# detectino.net
KiCad netlist of a schematic drawn in EAGLE
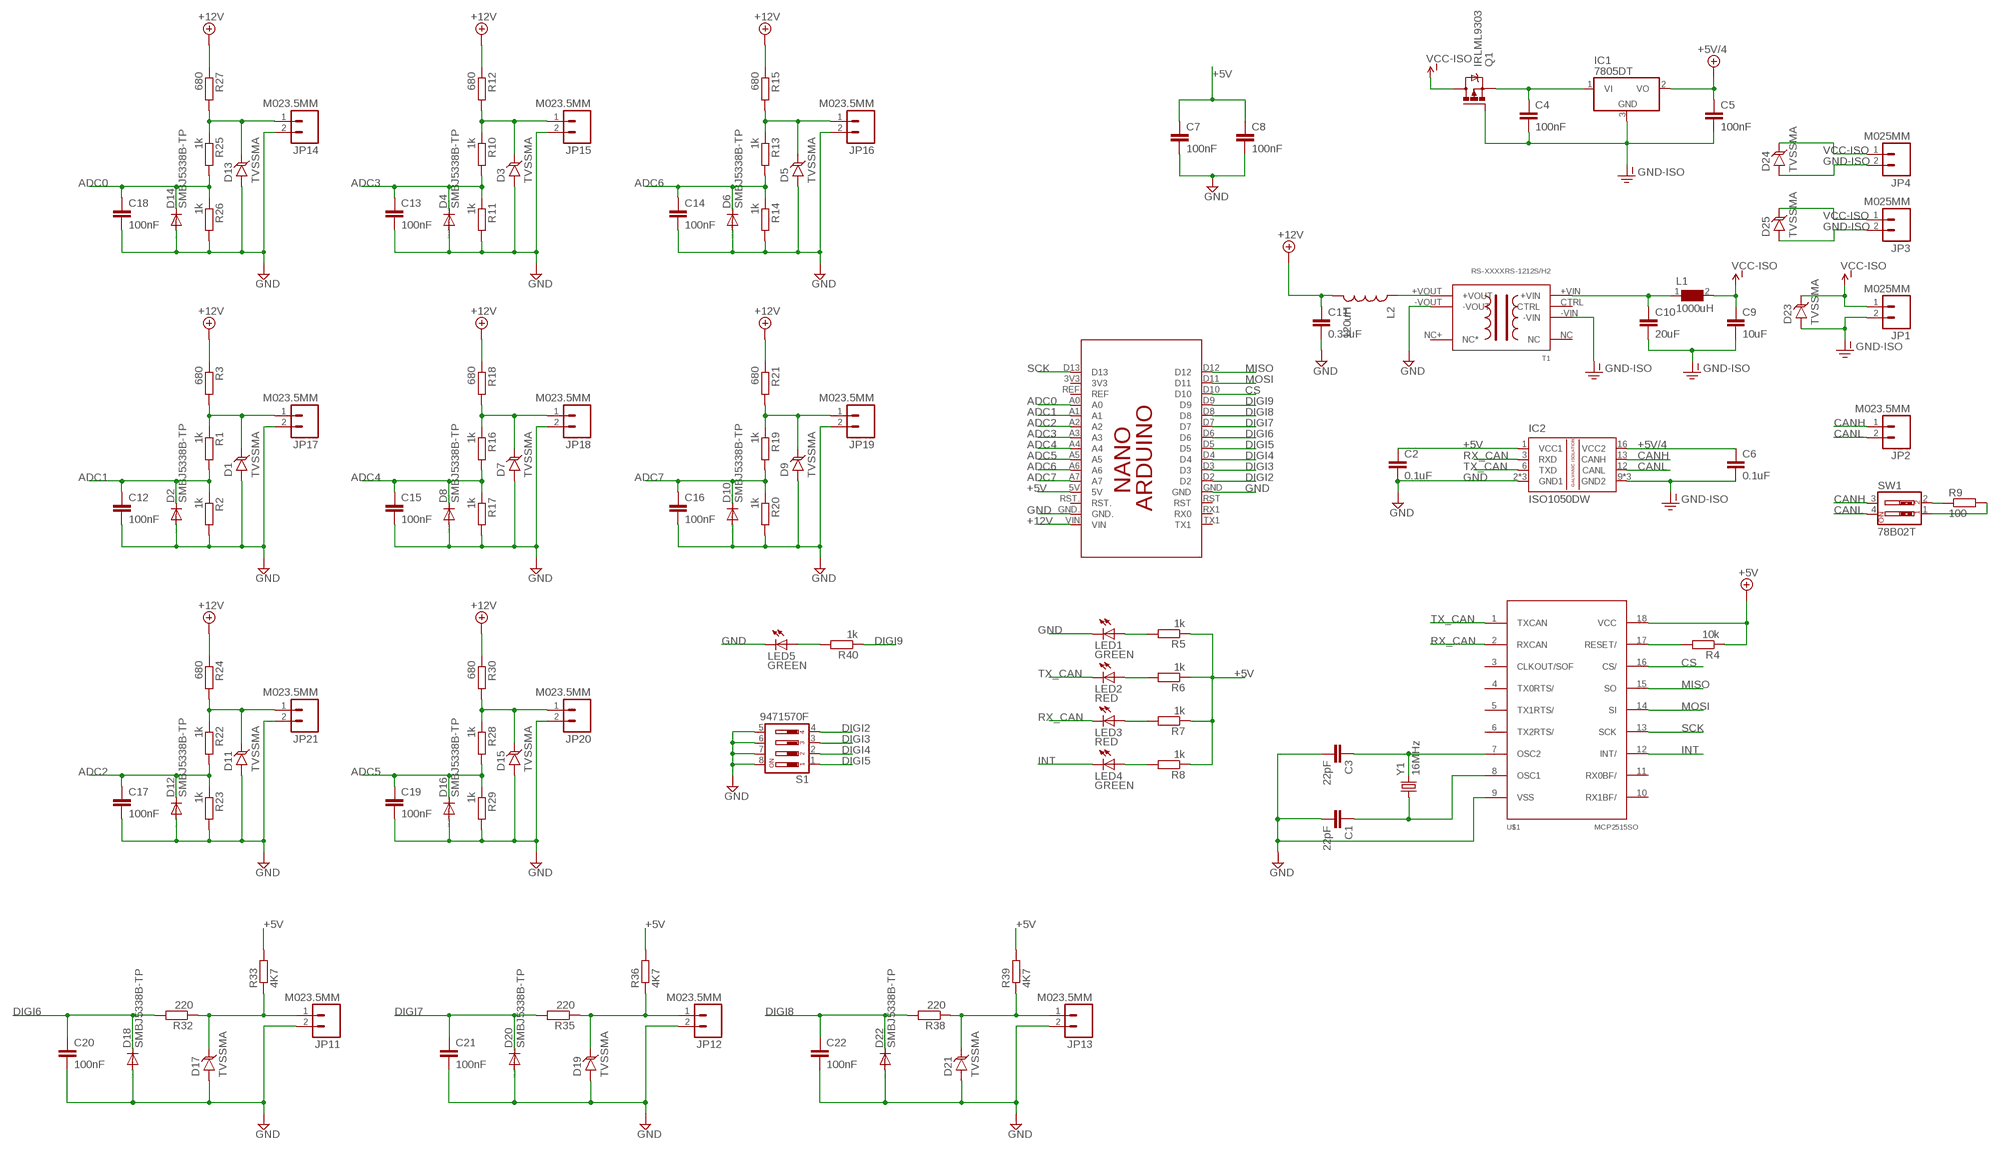
[diagram p0: schematic, sheet 1]

(export (version "E")
  (design (tool "Eeschema 10.0.6"))
  (components
    (comp (ref "C1")
      (value "22pF")
      (footprint "eagle-import:C0805K")
      (libsource (lib "eagle-import") (part "C-EUC0805K"))
    )
    (comp (ref "C2")
      (value "0.1uF")
      (footprint "eagle-import:C0805K")
      (libsource (lib "eagle-import") (part "C-EUC0805K"))
    )
    (comp (ref "C3")
      (value "22pF")
      (footprint "eagle-import:C0805K")
      (libsource (lib "eagle-import") (part "C-EUC0805K"))
    )
    (comp (ref "C4")
      (value "100nF")
      (footprint "eagle-import:C0805K")
      (libsource (lib "eagle-import") (part "C-EUC0805K"))
    )
    (comp (ref "C5")
      (value "100nF")
      (footprint "eagle-import:C0805K")
      (libsource (lib "eagle-import") (part "C-EUC0805K"))
    )
    (comp (ref "C6")
      (value "0.1uF")
      (footprint "eagle-import:C0805K")
      (libsource (lib "eagle-import") (part "C-EUC0805K"))
    )
    (comp (ref "C7")
      (value "100nF")
      (footprint "eagle-import:C0805K")
      (libsource (lib "eagle-import") (part "C-EUC0805K"))
    )
    (comp (ref "C8")
      (value "100nF")
      (footprint "eagle-import:C0805K")
      (libsource (lib "eagle-import") (part "C-EUC0805K"))
    )
    (comp (ref "C9")
      (value "10uF")
      (footprint "eagle-import:C0805K")
      (libsource (lib "eagle-import") (part "C-EUC0805K"))
    )
    (comp (ref "C10")
      (value "20uF")
      (footprint "eagle-import:C0805K")
      (libsource (lib "eagle-import") (part "C-EUC0805K"))
    )
    (comp (ref "C11")
      (value "0.33uF")
      (footprint "eagle-import:C0805K")
      (libsource (lib "eagle-import") (part "C-EUC0805K"))
    )
    (comp (ref "C12")
      (value "100nF")
      (footprint "eagle-import:C0805K")
      (libsource (lib "eagle-import") (part "C-EUC0805K"))
    )
    (comp (ref "C13")
      (value "100nF")
      (footprint "eagle-import:C0805K")
      (libsource (lib "eagle-import") (part "C-EUC0805K"))
    )
    (comp (ref "C14")
      (value "100nF")
      (footprint "eagle-import:C0805K")
      (libsource (lib "eagle-import") (part "C-EUC0805K"))
    )
    (comp (ref "C15")
      (value "100nF")
      (footprint "eagle-import:C0805K")
      (libsource (lib "eagle-import") (part "C-EUC0805K"))
    )
    (comp (ref "C16")
      (value "100nF")
      (footprint "eagle-import:C0805K")
      (libsource (lib "eagle-import") (part "C-EUC0805K"))
    )
    (comp (ref "C17")
      (value "100nF")
      (footprint "eagle-import:C0805K")
      (libsource (lib "eagle-import") (part "C-EUC0805K"))
    )
    (comp (ref "C18")
      (value "100nF")
      (footprint "eagle-import:C0805K")
      (libsource (lib "eagle-import") (part "C-EUC0805K"))
    )
    (comp (ref "C19")
      (value "100nF")
      (footprint "eagle-import:C0805K")
      (libsource (lib "eagle-import") (part "C-EUC0805K"))
    )
    (comp (ref "C20")
      (value "100nF")
      (footprint "eagle-import:C0805K")
      (libsource (lib "eagle-import") (part "C-EUC0805K"))
    )
    (comp (ref "C21")
      (value "100nF")
      (footprint "eagle-import:C0805K")
      (libsource (lib "eagle-import") (part "C-EUC0805K"))
    )
    (comp (ref "C22")
      (value "100nF")
      (footprint "eagle-import:C0805K")
      (libsource (lib "eagle-import") (part "C-EUC0805K"))
    )
    (comp (ref "D1")
      (value "TVSSMA")
      (footprint "eagle-import:SMA-DIODE")
      (libsource (lib "eagle-import") (part "TVSSMA"))
    )
    (comp (ref "D2")
      (value "SMBJ5338B-TP")
      (footprint "eagle-import:DO214AA")
      (libsource (lib "eagle-import") (part "DIODE-DO214AA"))
    )
    (comp (ref "D3")
      (value "TVSSMA")
      (footprint "eagle-import:SMA-DIODE")
      (libsource (lib "eagle-import") (part "TVSSMA"))
    )
    (comp (ref "D4")
      (value "SMBJ5338B-TP")
      (footprint "eagle-import:DO214AA")
      (libsource (lib "eagle-import") (part "DIODE-DO214AA"))
    )
    (comp (ref "D5")
      (value "TVSSMA")
      (footprint "eagle-import:SMA-DIODE")
      (libsource (lib "eagle-import") (part "TVSSMA"))
    )
    (comp (ref "D6")
      (value "SMBJ5338B-TP")
      (footprint "eagle-import:DO214AA")
      (libsource (lib "eagle-import") (part "DIODE-DO214AA"))
    )
    (comp (ref "D7")
      (value "TVSSMA")
      (footprint "eagle-import:SMA-DIODE")
      (libsource (lib "eagle-import") (part "TVSSMA"))
    )
    (comp (ref "D8")
      (value "SMBJ5338B-TP")
      (footprint "eagle-import:DO214AA")
      (libsource (lib "eagle-import") (part "DIODE-DO214AA"))
    )
    (comp (ref "D9")
      (value "TVSSMA")
      (footprint "eagle-import:SMA-DIODE")
      (libsource (lib "eagle-import") (part "TVSSMA"))
    )
    (comp (ref "D10")
      (value "SMBJ5338B-TP")
      (footprint "eagle-import:DO214AA")
      (libsource (lib "eagle-import") (part "DIODE-DO214AA"))
    )
    (comp (ref "D11")
      (value "TVSSMA")
      (footprint "eagle-import:SMA-DIODE")
      (libsource (lib "eagle-import") (part "TVSSMA"))
    )
    (comp (ref "D12")
      (value "SMBJ5338B-TP")
      (footprint "eagle-import:DO214AA")
      (libsource (lib "eagle-import") (part "DIODE-DO214AA"))
    )
    (comp (ref "D13")
      (value "TVSSMA")
      (footprint "eagle-import:SMA-DIODE")
      (libsource (lib "eagle-import") (part "TVSSMA"))
    )
    (comp (ref "D14")
      (value "SMBJ5338B-TP")
      (footprint "eagle-import:DO214AA")
      (libsource (lib "eagle-import") (part "DIODE-DO214AA"))
    )
    (comp (ref "D15")
      (value "TVSSMA")
      (footprint "eagle-import:SMA-DIODE")
      (libsource (lib "eagle-import") (part "TVSSMA"))
    )
    (comp (ref "D16")
      (value "SMBJ5338B-TP")
      (footprint "eagle-import:DO214AA")
      (libsource (lib "eagle-import") (part "DIODE-DO214AA"))
    )
    (comp (ref "D17")
      (value "TVSSMA")
      (footprint "eagle-import:SMA-DIODE")
      (libsource (lib "eagle-import") (part "TVSSMA"))
    )
    (comp (ref "D18")
      (value "SMBJ5338B-TP")
      (footprint "eagle-import:DO214AA")
      (libsource (lib "eagle-import") (part "DIODE-DO214AA"))
    )
    (comp (ref "D19")
      (value "TVSSMA")
      (footprint "eagle-import:SMA-DIODE")
      (libsource (lib "eagle-import") (part "TVSSMA"))
    )
    (comp (ref "D20")
      (value "SMBJ5338B-TP")
      (footprint "eagle-import:DO214AA")
      (libsource (lib "eagle-import") (part "DIODE-DO214AA"))
    )
    (comp (ref "D21")
      (value "TVSSMA")
      (footprint "eagle-import:SMA-DIODE")
      (libsource (lib "eagle-import") (part "TVSSMA"))
    )
    (comp (ref "D22")
      (value "SMBJ5338B-TP")
      (footprint "eagle-import:DO214AA")
      (libsource (lib "eagle-import") (part "DIODE-DO214AA"))
    )
    (comp (ref "D23")
      (value "TVSSMA")
      (footprint "eagle-import:SMA-DIODE")
      (libsource (lib "eagle-import") (part "TVSSMA"))
    )
    (comp (ref "D24")
      (value "TVSSMA")
      (footprint "eagle-import:SMA-DIODE")
      (libsource (lib "eagle-import") (part "TVSSMA"))
    )
    (comp (ref "D25")
      (value "TVSSMA")
      (footprint "eagle-import:SMA-DIODE")
      (libsource (lib "eagle-import") (part "TVSSMA"))
    )
    (comp (ref "IC1")
      (value "7805DT")
      (footprint "eagle-import:TO252")
      (libsource (lib "eagle-import") (part "78DT05"))
    )
    (comp (ref "IC2")
      (value "ISO1050DW")
      (footprint "eagle-import:SO-16DW")
      (libsource (lib "eagle-import") (part "ISO1050DW"))
    )
    (comp (ref "JP1")
      (value "M025MM")
      (footprint "eagle-import:SCREWTERMINAL-5MM-2")
      (libsource (lib "eagle-import") (part "M025MM"))
    )
    (comp (ref "JP2")
      (value "M023.5MM")
      (footprint "eagle-import:SCREWTERMINAL-3.5MM-2")
      (libsource (lib "eagle-import") (part "M023.5MM"))
    )
    (comp (ref "JP3")
      (value "M025MM")
      (footprint "eagle-import:SCREWTERMINAL-5MM-2")
      (libsource (lib "eagle-import") (part "M025MM"))
    )
    (comp (ref "JP4")
      (value "M025MM")
      (footprint "eagle-import:SCREWTERMINAL-5MM-2")
      (libsource (lib "eagle-import") (part "M025MM"))
    )
    (comp (ref "JP11")
      (value "M023.5MM")
      (footprint "eagle-import:SCREWTERMINAL-3.5MM-2")
      (libsource (lib "eagle-import") (part "M023.5MM"))
    )
    (comp (ref "JP12")
      (value "M023.5MM")
      (footprint "eagle-import:SCREWTERMINAL-3.5MM-2")
      (libsource (lib "eagle-import") (part "M023.5MM"))
    )
    (comp (ref "JP13")
      (value "M023.5MM")
      (footprint "eagle-import:SCREWTERMINAL-3.5MM-2")
      (libsource (lib "eagle-import") (part "M023.5MM"))
    )
    (comp (ref "JP14")
      (value "M023.5MM")
      (footprint "eagle-import:SCREWTERMINAL-3.5MM-2")
      (libsource (lib "eagle-import") (part "M023.5MM"))
    )
    (comp (ref "JP15")
      (value "M023.5MM")
      (footprint "eagle-import:SCREWTERMINAL-3.5MM-2")
      (libsource (lib "eagle-import") (part "M023.5MM"))
    )
    (comp (ref "JP16")
      (value "M023.5MM")
      (footprint "eagle-import:SCREWTERMINAL-3.5MM-2")
      (libsource (lib "eagle-import") (part "M023.5MM"))
    )
    (comp (ref "JP17")
      (value "M023.5MM")
      (footprint "eagle-import:SCREWTERMINAL-3.5MM-2")
      (libsource (lib "eagle-import") (part "M023.5MM"))
    )
    (comp (ref "JP18")
      (value "M023.5MM")
      (footprint "eagle-import:SCREWTERMINAL-3.5MM-2")
      (libsource (lib "eagle-import") (part "M023.5MM"))
    )
    (comp (ref "JP19")
      (value "M023.5MM")
      (footprint "eagle-import:SCREWTERMINAL-3.5MM-2")
      (libsource (lib "eagle-import") (part "M023.5MM"))
    )
    (comp (ref "JP20")
      (value "M023.5MM")
      (footprint "eagle-import:SCREWTERMINAL-3.5MM-2")
      (libsource (lib "eagle-import") (part "M023.5MM"))
    )
    (comp (ref "JP21")
      (value "M023.5MM")
      (footprint "eagle-import:SCREWTERMINAL-3.5MM-2")
      (libsource (lib "eagle-import") (part "M023.5MM"))
    )
    (comp (ref "L1")
      (value "1000uH")
      (footprint "eagle-import:WE-TIS_1111")
      (fields (field (name "MPN") "7447471102"))
      (libsource (lib "eagle-import") (part "WE-TIS_1111-7447471102"))
    )
    (comp (ref "L2")
      (value "120uH")
      (footprint "eagle-import:SDR0403")
      (libsource (lib "eagle-import") (part "INDUCTORSDR0403-560KL"))
    )
    (comp (ref "LED1")
      (value "GREEN")
      (footprint "eagle-import:SML0805")
      (libsource (lib "eagle-import") (part "LEDSML0805"))
    )
    (comp (ref "LED2")
      (value "RED")
      (footprint "eagle-import:SML0805")
      (libsource (lib "eagle-import") (part "LEDSML0805"))
    )
    (comp (ref "LED3")
      (value "RED")
      (footprint "eagle-import:SML0805")
      (libsource (lib "eagle-import") (part "LEDSML0805"))
    )
    (comp (ref "LED4")
      (value "GREEN")
      (footprint "eagle-import:SML0805")
      (libsource (lib "eagle-import") (part "LEDSML0805"))
    )
    (comp (ref "LED5")
      (value "GREEN")
      (footprint "eagle-import:SML0805")
      (libsource (lib "eagle-import") (part "LEDSML0805"))
    )
    (comp (ref "PCB2")
      (value "ARDUINO_NANO")
      (footprint "eagle-import:ARDUINO_NANO")
      (libsource (lib "eagle-import") (part "ARDUINO_NANO"))
    )
    (comp (ref "Q1")
      (value "IRLML9303")
      (footprint "eagle-import:MICRO3")
      (libsource (lib "eagle-import") (part "IRLML5203"))
    )
    (comp (ref "R1")
      (value "1k")
      (footprint "eagle-import:0204_5")
      (libsource (lib "eagle-import") (part "R-EU_0204/5"))
    )
    (comp (ref "R2")
      (value "1k")
      (footprint "eagle-import:0204_5")
      (libsource (lib "eagle-import") (part "R-EU_0204/5"))
    )
    (comp (ref "R3")
      (value "680")
      (footprint "eagle-import:0204_5")
      (libsource (lib "eagle-import") (part "R-EU_0204/5"))
    )
    (comp (ref "R4")
      (value "10k")
      (footprint "eagle-import:R0805W")
      (libsource (lib "eagle-import") (part "R-EU_R0805W"))
    )
    (comp (ref "R5")
      (value "1k")
      (footprint "eagle-import:0204_5")
      (libsource (lib "eagle-import") (part "R-EU_0204/5"))
    )
    (comp (ref "R6")
      (value "1k")
      (footprint "eagle-import:0204_5")
      (libsource (lib "eagle-import") (part "R-EU_0204/5"))
    )
    (comp (ref "R7")
      (value "1k")
      (footprint "eagle-import:0204_5")
      (libsource (lib "eagle-import") (part "R-EU_0204/5"))
    )
    (comp (ref "R8")
      (value "1k")
      (footprint "eagle-import:0204_5")
      (libsource (lib "eagle-import") (part "R-EU_0204/5"))
    )
    (comp (ref "R9")
      (value "100")
      (footprint "eagle-import:R0805W")
      (libsource (lib "eagle-import") (part "R-EU_R0805W"))
    )
    (comp (ref "R10")
      (value "1k")
      (footprint "eagle-import:0204_5")
      (libsource (lib "eagle-import") (part "R-EU_0204/5"))
    )
    (comp (ref "R11")
      (value "1k")
      (footprint "eagle-import:0204_5")
      (libsource (lib "eagle-import") (part "R-EU_0204/5"))
    )
    (comp (ref "R12")
      (value "680")
      (footprint "eagle-import:0204_5")
      (libsource (lib "eagle-import") (part "R-EU_0204/5"))
    )
    (comp (ref "R13")
      (value "1k")
      (footprint "eagle-import:0204_5")
      (libsource (lib "eagle-import") (part "R-EU_0204/5"))
    )
    (comp (ref "R14")
      (value "1k")
      (footprint "eagle-import:0204_5")
      (libsource (lib "eagle-import") (part "R-EU_0204/5"))
    )
    (comp (ref "R15")
      (value "680")
      (footprint "eagle-import:0204_5")
      (libsource (lib "eagle-import") (part "R-EU_0204/5"))
    )
    (comp (ref "R16")
      (value "1k")
      (footprint "eagle-import:0204_5")
      (libsource (lib "eagle-import") (part "R-EU_0204/5"))
    )
    (comp (ref "R17")
      (value "1k")
      (footprint "eagle-import:0204_5")
      (libsource (lib "eagle-import") (part "R-EU_0204/5"))
    )
    (comp (ref "R18")
      (value "680")
      (footprint "eagle-import:0204_5")
      (libsource (lib "eagle-import") (part "R-EU_0204/5"))
    )
    (comp (ref "R19")
      (value "1k")
      (footprint "eagle-import:0204_5")
      (libsource (lib "eagle-import") (part "R-EU_0204/5"))
    )
    (comp (ref "R20")
      (value "1k")
      (footprint "eagle-import:0204_5")
      (libsource (lib "eagle-import") (part "R-EU_0204/5"))
    )
    (comp (ref "R21")
      (value "680")
      (footprint "eagle-import:0204_5")
      (libsource (lib "eagle-import") (part "R-EU_0204/5"))
    )
    (comp (ref "R22")
      (value "1k")
      (footprint "eagle-import:0204_5")
      (libsource (lib "eagle-import") (part "R-EU_0204/5"))
    )
    (comp (ref "R23")
      (value "1k")
      (footprint "eagle-import:0204_5")
      (libsource (lib "eagle-import") (part "R-EU_0204/5"))
    )
    (comp (ref "R24")
      (value "680")
      (footprint "eagle-import:0204_5")
      (libsource (lib "eagle-import") (part "R-EU_0204/5"))
    )
    (comp (ref "R25")
      (value "1k")
      (footprint "eagle-import:0204_5")
      (libsource (lib "eagle-import") (part "R-EU_0204/5"))
    )
    (comp (ref "R26")
      (value "1k")
      (footprint "eagle-import:0204_5")
      (libsource (lib "eagle-import") (part "R-EU_0204/5"))
    )
    (comp (ref "R27")
      (value "680")
      (footprint "eagle-import:0204_5")
      (libsource (lib "eagle-import") (part "R-EU_0204/5"))
    )
    (comp (ref "R28")
      (value "1k")
      (footprint "eagle-import:0204_5")
      (libsource (lib "eagle-import") (part "R-EU_0204/5"))
    )
    (comp (ref "R29")
      (value "1k")
      (footprint "eagle-import:0204_5")
      (libsource (lib "eagle-import") (part "R-EU_0204/5"))
    )
    (comp (ref "R30")
      (value "680")
      (footprint "eagle-import:0204_5")
      (libsource (lib "eagle-import") (part "R-EU_0204/5"))
    )
    (comp (ref "R32")
      (value "220")
      (footprint "eagle-import:0204_5")
      (libsource (lib "eagle-import") (part "R-EU_0204/5"))
    )
    (comp (ref "R33")
      (value "4K7")
      (footprint "eagle-import:0204_5")
      (libsource (lib "eagle-import") (part "R-EU_0204/5"))
    )
    (comp (ref "R35")
      (value "220")
      (footprint "eagle-import:0204_5")
      (libsource (lib "eagle-import") (part "R-EU_0204/5"))
    )
    (comp (ref "R36")
      (value "4K7")
      (footprint "eagle-import:0204_5")
      (libsource (lib "eagle-import") (part "R-EU_0204/5"))
    )
    (comp (ref "R38")
      (value "220")
      (footprint "eagle-import:0204_5")
      (libsource (lib "eagle-import") (part "R-EU_0204/5"))
    )
    (comp (ref "R39")
      (value "4K7")
      (footprint "eagle-import:0204_5")
      (libsource (lib "eagle-import") (part "R-EU_0204/5"))
    )
    (comp (ref "R40")
      (value "1k")
      (footprint "eagle-import:0204_5")
      (libsource (lib "eagle-import") (part "R-EU_0204/5"))
    )
    (comp (ref "S1")
      (value "9471570F")
      (footprint "eagle-import:DS-04")
      (libsource (lib "eagle-import") (part "DS04"))
    )
    (comp (ref "SW1")
      (value "78B02T")
      (footprint "eagle-import:DIPSWITCH-02")
      (libsource (lib "eagle-import") (part "SW_DIP-2"))
    )
    (comp (ref "T1")
      (value "RS-XXXXRS-1212S/H2")
      (footprint "eagle-import:SIP8")
      (libsource (lib "eagle-import") (part "RS-XXXXRS-1212S/H2"))
    )
    (comp (ref "U$1")
      (value "MCP2515SO")
      (footprint "eagle-import:SO18L")
      (libsource (lib "eagle-import") (part "MCP2515SO"))
    )
    (comp (ref "Y1")
      (value "16MHz")
      (footprint "eagle-import:HC49US")
      (libsource (lib "eagle-import") (part "CRYSTALHC49US"))
    )
  )
  (nets
    (net (code "1") (name "+5V") (class "Default")
      (node (ref "C2") (pin "1") (pinfunction "1_1") (pintype "passive"))
      (node (ref "C7") (pin "1") (pinfunction "1_1") (pintype "passive"))
      (node (ref "C8") (pin "1") (pinfunction "1_1") (pintype "passive"))
      (node (ref "IC2") (pin "1") (pinfunction "VCC1_1") (pintype "input"))
      (node (ref "PCB2") (pin "5V") (pinfunction "5V_5V") (pintype "bidirectional"))
      (node (ref "R33") (pin "2") (pinfunction "2_2") (pintype "passive"))
      (node (ref "R36") (pin "2") (pinfunction "2_2") (pintype "passive"))
      (node (ref "R39") (pin "2") (pinfunction "2_2") (pintype "passive"))
      (node (ref "R4") (pin "1") (pinfunction "1_1") (pintype "passive"))
      (node (ref "R5") (pin "1") (pinfunction "1_1") (pintype "passive"))
      (node (ref "R6") (pin "1") (pinfunction "1_1") (pintype "passive"))
      (node (ref "R7") (pin "1") (pinfunction "1_1") (pintype "passive"))
      (node (ref "R8") (pin "1") (pinfunction "1_1") (pintype "passive"))
      (node (ref "U$1") (pin "18") (pinfunction "VCC_18") (pintype "power_in"))
    )
    (net (code "2") (name "+5V{slash}4") (class "Default")
      (node (ref "C5") (pin "1") (pinfunction "1_1") (pintype "passive"))
      (node (ref "C6") (pin "1") (pinfunction "1_1") (pintype "passive"))
      (node (ref "IC1") (pin "2") (pinfunction "VO_2") (pintype "passive"))
      (node (ref "IC2") (pin "16") (pinfunction "VCC2_16") (pintype "input"))
    )
    (net (code "3") (name "+12V") (class "Default")
      (node (ref "C11") (pin "1") (pinfunction "1_1") (pintype "passive"))
      (node (ref "L2") (pin "P$2") (pinfunction "2_P$2") (pintype "passive"))
      (node (ref "PCB2") (pin "VIN") (pinfunction "VIN_VIN") (pintype "bidirectional"))
      (node (ref "R12") (pin "1") (pinfunction "1_1") (pintype "passive"))
      (node (ref "R15") (pin "1") (pinfunction "1_1") (pintype "passive"))
      (node (ref "R18") (pin "1") (pinfunction "1_1") (pintype "passive"))
      (node (ref "R21") (pin "1") (pinfunction "1_1") (pintype "passive"))
      (node (ref "R24") (pin "1") (pinfunction "1_1") (pintype "passive"))
      (node (ref "R27") (pin "1") (pinfunction "1_1") (pintype "passive"))
      (node (ref "R3") (pin "1") (pinfunction "1_1") (pintype "passive"))
      (node (ref "R30") (pin "1") (pinfunction "1_1") (pintype "passive"))
    )
    (net (code "4") (name "/ADC0") (class "Default")
      (node (ref "C18") (pin "1") (pinfunction "1_1") (pintype "passive"))
      (node (ref "D14") (pin "C") (pinfunction "C_C") (pintype "passive"))
      (node (ref "PCB2") (pin "A0") (pinfunction "A0_A0") (pintype "bidirectional"))
      (node (ref "R25") (pin "2") (pinfunction "2_2") (pintype "passive"))
      (node (ref "R26") (pin "1") (pinfunction "1_1") (pintype "passive"))
    )
    (net (code "5") (name "/ADC1") (class "Default")
      (node (ref "C12") (pin "1") (pinfunction "1_1") (pintype "passive"))
      (node (ref "D2") (pin "C") (pinfunction "C_C") (pintype "passive"))
      (node (ref "PCB2") (pin "A1") (pinfunction "A1_A1") (pintype "bidirectional"))
      (node (ref "R1") (pin "2") (pinfunction "2_2") (pintype "passive"))
      (node (ref "R2") (pin "1") (pinfunction "1_1") (pintype "passive"))
    )
    (net (code "6") (name "/ADC2") (class "Default")
      (node (ref "C17") (pin "1") (pinfunction "1_1") (pintype "passive"))
      (node (ref "D12") (pin "C") (pinfunction "C_C") (pintype "passive"))
      (node (ref "PCB2") (pin "A2") (pinfunction "A2_A2") (pintype "bidirectional"))
      (node (ref "R22") (pin "2") (pinfunction "2_2") (pintype "passive"))
      (node (ref "R23") (pin "1") (pinfunction "1_1") (pintype "passive"))
    )
    (net (code "7") (name "/ADC3") (class "Default")
      (node (ref "C13") (pin "1") (pinfunction "1_1") (pintype "passive"))
      (node (ref "D4") (pin "C") (pinfunction "C_C") (pintype "passive"))
      (node (ref "PCB2") (pin "A3") (pinfunction "A3_A3") (pintype "bidirectional"))
      (node (ref "R10") (pin "2") (pinfunction "2_2") (pintype "passive"))
      (node (ref "R11") (pin "1") (pinfunction "1_1") (pintype "passive"))
    )
    (net (code "8") (name "/ADC4") (class "Default")
      (node (ref "C15") (pin "1") (pinfunction "1_1") (pintype "passive"))
      (node (ref "D8") (pin "C") (pinfunction "C_C") (pintype "passive"))
      (node (ref "PCB2") (pin "A4") (pinfunction "A4_A4") (pintype "bidirectional"))
      (node (ref "R16") (pin "2") (pinfunction "2_2") (pintype "passive"))
      (node (ref "R17") (pin "1") (pinfunction "1_1") (pintype "passive"))
    )
    (net (code "9") (name "/ADC5") (class "Default")
      (node (ref "C19") (pin "1") (pinfunction "1_1") (pintype "passive"))
      (node (ref "D16") (pin "C") (pinfunction "C_C") (pintype "passive"))
      (node (ref "PCB2") (pin "A5") (pinfunction "A5_A5") (pintype "bidirectional"))
      (node (ref "R28") (pin "2") (pinfunction "2_2") (pintype "passive"))
      (node (ref "R29") (pin "1") (pinfunction "1_1") (pintype "passive"))
    )
    (net (code "10") (name "/ADC6") (class "Default")
      (node (ref "C14") (pin "1") (pinfunction "1_1") (pintype "passive"))
      (node (ref "D6") (pin "C") (pinfunction "C_C") (pintype "passive"))
      (node (ref "PCB2") (pin "A6") (pinfunction "A6_A6") (pintype "bidirectional"))
      (node (ref "R13") (pin "2") (pinfunction "2_2") (pintype "passive"))
      (node (ref "R14") (pin "1") (pinfunction "1_1") (pintype "passive"))
    )
    (net (code "11") (name "/ADC7") (class "Default")
      (node (ref "C16") (pin "1") (pinfunction "1_1") (pintype "passive"))
      (node (ref "D10") (pin "C") (pinfunction "C_C") (pintype "passive"))
      (node (ref "PCB2") (pin "A7") (pinfunction "A7_A7") (pintype "bidirectional"))
      (node (ref "R19") (pin "2") (pinfunction "2_2") (pintype "passive"))
      (node (ref "R20") (pin "1") (pinfunction "1_1") (pintype "passive"))
    )
    (net (code "12") (name "/CANH") (class "Default")
      (node (ref "IC2") (pin "13") (pinfunction "CANH_13") (pintype "input"))
      (node (ref "JP2") (pin "1") (pinfunction "1_1") (pintype "passive"))
      (node (ref "SW1") (pin "3") (pinfunction "3_3") (pintype "passive"))
    )
    (net (code "13") (name "/CANL") (class "Default")
      (node (ref "IC2") (pin "12") (pinfunction "CANL_12") (pintype "input"))
      (node (ref "JP2") (pin "2") (pinfunction "2_2") (pintype "passive"))
      (node (ref "SW1") (pin "4") (pinfunction "4_4") (pintype "passive"))
    )
    (net (code "14") (name "/CS") (class "Default")
      (node (ref "PCB2") (pin "D10") (pinfunction "D10_D10") (pintype "bidirectional"))
      (node (ref "U$1") (pin "16") (pinfunction "CS/_16") (pintype "input"))
    )
    (net (code "15") (name "/DIGI2") (class "Default")
      (node (ref "PCB2") (pin "D2") (pinfunction "D2_D2") (pintype "bidirectional"))
      (node (ref "S1") (pin "4") (pinfunction "4_4") (pintype "passive"))
    )
    (net (code "16") (name "/DIGI3") (class "Default")
      (node (ref "PCB2") (pin "D3") (pinfunction "D3_D3") (pintype "bidirectional"))
      (node (ref "S1") (pin "3") (pinfunction "3_3") (pintype "passive"))
    )
    (net (code "17") (name "/DIGI4") (class "Default")
      (node (ref "PCB2") (pin "D4") (pinfunction "D4_D4") (pintype "bidirectional"))
      (node (ref "S1") (pin "2") (pinfunction "2_2") (pintype "passive"))
    )
    (net (code "18") (name "/DIGI5") (class "Default")
      (node (ref "PCB2") (pin "D5") (pinfunction "D5_D5") (pintype "bidirectional"))
      (node (ref "S1") (pin "1") (pinfunction "1_1") (pintype "passive"))
    )
    (net (code "19") (name "/DIGI6") (class "Default")
      (node (ref "C20") (pin "1") (pinfunction "1_1") (pintype "passive"))
      (node (ref "D18") (pin "C") (pinfunction "C_C") (pintype "passive"))
      (node (ref "PCB2") (pin "D6") (pinfunction "D6_D6") (pintype "bidirectional"))
      (node (ref "R32") (pin "2") (pinfunction "2_2") (pintype "passive"))
    )
    (net (code "20") (name "/DIGI7") (class "Default")
      (node (ref "C21") (pin "1") (pinfunction "1_1") (pintype "passive"))
      (node (ref "D20") (pin "C") (pinfunction "C_C") (pintype "passive"))
      (node (ref "PCB2") (pin "D7") (pinfunction "D7_D7") (pintype "bidirectional"))
      (node (ref "R35") (pin "2") (pinfunction "2_2") (pintype "passive"))
    )
    (net (code "21") (name "/DIGI8") (class "Default")
      (node (ref "C22") (pin "1") (pinfunction "1_1") (pintype "passive"))
      (node (ref "D22") (pin "C") (pinfunction "C_C") (pintype "passive"))
      (node (ref "PCB2") (pin "D8") (pinfunction "D8_D8") (pintype "bidirectional"))
      (node (ref "R38") (pin "2") (pinfunction "2_2") (pintype "passive"))
    )
    (net (code "22") (name "/DIGI9") (class "Default")
      (node (ref "PCB2") (pin "D9") (pinfunction "D9_D9") (pintype "bidirectional"))
      (node (ref "R40") (pin "1") (pinfunction "1_1") (pintype "passive"))
    )
    (net (code "23") (name "/INT") (class "Default")
      (node (ref "LED4") (pin "C") (pinfunction "C_C") (pintype "passive"))
      (node (ref "U$1") (pin "12") (pinfunction "INT/_12") (pintype "output"))
    )
    (net (code "24") (name "/MISO") (class "Default")
      (node (ref "PCB2") (pin "D12") (pinfunction "D12_D12") (pintype "bidirectional"))
      (node (ref "U$1") (pin "15") (pinfunction "SO_15") (pintype "output"))
    )
    (net (code "25") (name "/MOSI") (class "Default")
      (node (ref "PCB2") (pin "D11") (pinfunction "D11_D11") (pintype "bidirectional"))
      (node (ref "U$1") (pin "14") (pinfunction "SI_14") (pintype "input"))
    )
    (net (code "26") (name "/RX_CAN") (class "Default")
      (node (ref "IC2") (pin "3") (pinfunction "RXD_3") (pintype "input"))
      (node (ref "LED3") (pin "C") (pinfunction "C_C") (pintype "passive"))
      (node (ref "U$1") (pin "2") (pinfunction "RXCAN_2") (pintype "input"))
    )
    (net (code "27") (name "/SCK") (class "Default")
      (node (ref "PCB2") (pin "D13") (pinfunction "D13_D13") (pintype "bidirectional"))
      (node (ref "U$1") (pin "13") (pinfunction "SCK_13") (pintype "input"))
    )
    (net (code "28") (name "/TX_CAN") (class "Default")
      (node (ref "IC2") (pin "6") (pinfunction "TXD_6") (pintype "input"))
      (node (ref "LED2") (pin "C") (pinfunction "C_C") (pintype "passive"))
      (node (ref "U$1") (pin "1") (pinfunction "TXCAN_1") (pintype "output"))
    )
    (net (code "29") (name "GND") (class "Default")
      (node (ref "C1") (pin "2") (pinfunction "2_2") (pintype "passive"))
      (node (ref "C11") (pin "2") (pinfunction "2_2") (pintype "passive"))
      (node (ref "C12") (pin "2") (pinfunction "2_2") (pintype "passive"))
      (node (ref "C13") (pin "2") (pinfunction "2_2") (pintype "passive"))
      (node (ref "C14") (pin "2") (pinfunction "2_2") (pintype "passive"))
      (node (ref "C15") (pin "2") (pinfunction "2_2") (pintype "passive"))
      (node (ref "C16") (pin "2") (pinfunction "2_2") (pintype "passive"))
      (node (ref "C17") (pin "2") (pinfunction "2_2") (pintype "passive"))
      (node (ref "C18") (pin "2") (pinfunction "2_2") (pintype "passive"))
      (node (ref "C19") (pin "2") (pinfunction "2_2") (pintype "passive"))
      (node (ref "C2") (pin "2") (pinfunction "2_2") (pintype "passive"))
      (node (ref "C20") (pin "2") (pinfunction "2_2") (pintype "passive"))
      (node (ref "C21") (pin "2") (pinfunction "2_2") (pintype "passive"))
      (node (ref "C22") (pin "2") (pinfunction "2_2") (pintype "passive"))
      (node (ref "C3") (pin "2") (pinfunction "2_2") (pintype "passive"))
      (node (ref "C7") (pin "2") (pinfunction "2_2") (pintype "passive"))
      (node (ref "C8") (pin "2") (pinfunction "2_2") (pintype "passive"))
      (node (ref "D1") (pin "A") (pinfunction "A_A") (pintype "passive"))
      (node (ref "D10") (pin "A") (pinfunction "A_A") (pintype "passive"))
      (node (ref "D11") (pin "A") (pinfunction "A_A") (pintype "passive"))
      (node (ref "D12") (pin "A") (pinfunction "A_A") (pintype "passive"))
      (node (ref "D13") (pin "A") (pinfunction "A_A") (pintype "passive"))
      (node (ref "D14") (pin "A") (pinfunction "A_A") (pintype "passive"))
      (node (ref "D15") (pin "A") (pinfunction "A_A") (pintype "passive"))
      (node (ref "D16") (pin "A") (pinfunction "A_A") (pintype "passive"))
      (node (ref "D17") (pin "A") (pinfunction "A_A") (pintype "passive"))
      (node (ref "D18") (pin "A") (pinfunction "A_A") (pintype "passive"))
      (node (ref "D19") (pin "A") (pinfunction "A_A") (pintype "passive"))
      (node (ref "D2") (pin "A") (pinfunction "A_A") (pintype "passive"))
      (node (ref "D20") (pin "A") (pinfunction "A_A") (pintype "passive"))
      (node (ref "D21") (pin "A") (pinfunction "A_A") (pintype "passive"))
      (node (ref "D22") (pin "A") (pinfunction "A_A") (pintype "passive"))
      (node (ref "D3") (pin "A") (pinfunction "A_A") (pintype "passive"))
      (node (ref "D4") (pin "A") (pinfunction "A_A") (pintype "passive"))
      (node (ref "D5") (pin "A") (pinfunction "A_A") (pintype "passive"))
      (node (ref "D6") (pin "A") (pinfunction "A_A") (pintype "passive"))
      (node (ref "D7") (pin "A") (pinfunction "A_A") (pintype "passive"))
      (node (ref "D8") (pin "A") (pinfunction "A_A") (pintype "passive"))
      (node (ref "D9") (pin "A") (pinfunction "A_A") (pintype "passive"))
      (node (ref "IC2") (pin "2") (pinfunction "GND1_2") (pintype "input"))
      (node (ref "IC2") (pin "7") (pinfunction "GND1_7") (pintype "input"))
      (node (ref "IC2") (pin "8") (pinfunction "GND1_8") (pintype "input"))
      (node (ref "JP11") (pin "2") (pinfunction "2_2") (pintype "passive"))
      (node (ref "JP12") (pin "2") (pinfunction "2_2") (pintype "passive"))
      (node (ref "JP13") (pin "2") (pinfunction "2_2") (pintype "passive"))
      (node (ref "JP14") (pin "2") (pinfunction "2_2") (pintype "passive"))
      (node (ref "JP15") (pin "2") (pinfunction "2_2") (pintype "passive"))
      (node (ref "JP16") (pin "2") (pinfunction "2_2") (pintype "passive"))
      (node (ref "JP17") (pin "2") (pinfunction "2_2") (pintype "passive"))
      (node (ref "JP18") (pin "2") (pinfunction "2_2") (pintype "passive"))
      (node (ref "JP19") (pin "2") (pinfunction "2_2") (pintype "passive"))
      (node (ref "JP20") (pin "2") (pinfunction "2_2") (pintype "passive"))
      (node (ref "JP21") (pin "2") (pinfunction "2_2") (pintype "passive"))
      (node (ref "LED1") (pin "C") (pinfunction "C_C") (pintype "passive"))
      (node (ref "LED5") (pin "C") (pinfunction "C_C") (pintype "passive"))
      (node (ref "PCB2") (pin "GND") (pinfunction "GND_GND") (pintype "bidirectional"))
      (node (ref "PCB2") (pin "GND.") (pinfunction "GND._GND.") (pintype "bidirectional"))
      (node (ref "R11") (pin "2") (pinfunction "2_2") (pintype "passive"))
      (node (ref "R14") (pin "2") (pinfunction "2_2") (pintype "passive"))
      (node (ref "R17") (pin "2") (pinfunction "2_2") (pintype "passive"))
      (node (ref "R2") (pin "2") (pinfunction "2_2") (pintype "passive"))
      (node (ref "R20") (pin "2") (pinfunction "2_2") (pintype "passive"))
      (node (ref "R23") (pin "2") (pinfunction "2_2") (pintype "passive"))
      (node (ref "R26") (pin "2") (pinfunction "2_2") (pintype "passive"))
      (node (ref "R29") (pin "2") (pinfunction "2_2") (pintype "passive"))
      (node (ref "S1") (pin "5") (pinfunction "5_5") (pintype "passive"))
      (node (ref "S1") (pin "6") (pinfunction "6_6") (pintype "passive"))
      (node (ref "S1") (pin "7") (pinfunction "7_7") (pintype "passive"))
      (node (ref "S1") (pin "8") (pinfunction "8_8") (pintype "passive"))
      (node (ref "T1") (pin "-VOUT") (pinfunction "-VOUT_-VOUT") (pintype "bidirectional"))
      (node (ref "U$1") (pin "9") (pinfunction "VSS_9") (pintype "power_in"))
    )
    (net (code "30") (name "GND-ISO") (class "Default")
      (node (ref "C10") (pin "2") (pinfunction "2_2") (pintype "passive"))
      (node (ref "C4") (pin "2") (pinfunction "2_2") (pintype "passive"))
      (node (ref "C5") (pin "2") (pinfunction "2_2") (pintype "passive"))
      (node (ref "C6") (pin "2") (pinfunction "2_2") (pintype "passive"))
      (node (ref "C9") (pin "2") (pinfunction "2_2") (pintype "passive"))
      (node (ref "D23") (pin "A") (pinfunction "A_A") (pintype "passive"))
      (node (ref "D24") (pin "A") (pinfunction "A_A") (pintype "passive"))
      (node (ref "D25") (pin "A") (pinfunction "A_A") (pintype "passive"))
      (node (ref "IC1") (pin "3") (pinfunction "GND_3") (pintype "passive"))
      (node (ref "IC2") (pin "10") (pinfunction "GND2_10") (pintype "input"))
      (node (ref "IC2") (pin "15") (pinfunction "GND2_15") (pintype "input"))
      (node (ref "IC2") (pin "9") (pinfunction "GND2_9") (pintype "input"))
      (node (ref "JP1") (pin "2") (pinfunction "2_2") (pintype "passive"))
      (node (ref "JP3") (pin "2") (pinfunction "2_2") (pintype "passive"))
      (node (ref "JP4") (pin "2") (pinfunction "2_2") (pintype "passive"))
      (node (ref "Q1") (pin "1") (pinfunction "G_1") (pintype "passive"))
      (node (ref "T1") (pin "-VIN") (pinfunction "-VIN_-VIN") (pintype "bidirectional"))
    )
    (net (code "31") (name "Net-(C10-Pad1)") (class "Default")
      (node (ref "C10") (pin "1") (pinfunction "1_1") (pintype "passive"))
      (node (ref "L1") (pin "1") (pinfunction "1_1") (pintype "passive"))
      (node (ref "T1") (pin "+VIN") (pinfunction "+VIN_+VIN") (pintype "bidirectional"))
    )
    (net (code "32") (name "Net-(D1-PadC)") (class "Default")
      (node (ref "D1") (pin "C") (pinfunction "C_C") (pintype "passive"))
      (node (ref "JP17") (pin "1") (pinfunction "1_1") (pintype "passive"))
      (node (ref "R1") (pin "1") (pinfunction "1_1") (pintype "passive"))
      (node (ref "R3") (pin "2") (pinfunction "2_2") (pintype "passive"))
    )
    (net (code "33") (name "Net-(D3-PadC)") (class "Default")
      (node (ref "D3") (pin "C") (pinfunction "C_C") (pintype "passive"))
      (node (ref "JP15") (pin "1") (pinfunction "1_1") (pintype "passive"))
      (node (ref "R10") (pin "1") (pinfunction "1_1") (pintype "passive"))
      (node (ref "R12") (pin "2") (pinfunction "2_2") (pintype "passive"))
    )
    (net (code "34") (name "Net-(D5-PadC)") (class "Default")
      (node (ref "D5") (pin "C") (pinfunction "C_C") (pintype "passive"))
      (node (ref "JP16") (pin "1") (pinfunction "1_1") (pintype "passive"))
      (node (ref "R13") (pin "1") (pinfunction "1_1") (pintype "passive"))
      (node (ref "R15") (pin "2") (pinfunction "2_2") (pintype "passive"))
    )
    (net (code "35") (name "Net-(D7-PadC)") (class "Default")
      (node (ref "D7") (pin "C") (pinfunction "C_C") (pintype "passive"))
      (node (ref "JP18") (pin "1") (pinfunction "1_1") (pintype "passive"))
      (node (ref "R16") (pin "1") (pinfunction "1_1") (pintype "passive"))
      (node (ref "R18") (pin "2") (pinfunction "2_2") (pintype "passive"))
    )
    (net (code "36") (name "Net-(D9-PadC)") (class "Default")
      (node (ref "D9") (pin "C") (pinfunction "C_C") (pintype "passive"))
      (node (ref "JP19") (pin "1") (pinfunction "1_1") (pintype "passive"))
      (node (ref "R19") (pin "1") (pinfunction "1_1") (pintype "passive"))
      (node (ref "R21") (pin "2") (pinfunction "2_2") (pintype "passive"))
    )
    (net (code "37") (name "Net-(D11-PadC)") (class "Default")
      (node (ref "D11") (pin "C") (pinfunction "C_C") (pintype "passive"))
      (node (ref "JP21") (pin "1") (pinfunction "1_1") (pintype "passive"))
      (node (ref "R22") (pin "1") (pinfunction "1_1") (pintype "passive"))
      (node (ref "R24") (pin "2") (pinfunction "2_2") (pintype "passive"))
    )
    (net (code "38") (name "Net-(D13-PadC)") (class "Default")
      (node (ref "D13") (pin "C") (pinfunction "C_C") (pintype "passive"))
      (node (ref "JP14") (pin "1") (pinfunction "1_1") (pintype "passive"))
      (node (ref "R25") (pin "1") (pinfunction "1_1") (pintype "passive"))
      (node (ref "R27") (pin "2") (pinfunction "2_2") (pintype "passive"))
    )
    (net (code "39") (name "Net-(D15-PadC)") (class "Default")
      (node (ref "D15") (pin "C") (pinfunction "C_C") (pintype "passive"))
      (node (ref "JP20") (pin "1") (pinfunction "1_1") (pintype "passive"))
      (node (ref "R28") (pin "1") (pinfunction "1_1") (pintype "passive"))
      (node (ref "R30") (pin "2") (pinfunction "2_2") (pintype "passive"))
    )
    (net (code "40") (name "Net-(D17-PadC)") (class "Default")
      (node (ref "D17") (pin "C") (pinfunction "C_C") (pintype "passive"))
      (node (ref "JP11") (pin "1") (pinfunction "1_1") (pintype "passive"))
      (node (ref "R32") (pin "1") (pinfunction "1_1") (pintype "passive"))
      (node (ref "R33") (pin "1") (pinfunction "1_1") (pintype "passive"))
    )
    (net (code "41") (name "Net-(D19-PadC)") (class "Default")
      (node (ref "D19") (pin "C") (pinfunction "C_C") (pintype "passive"))
      (node (ref "JP12") (pin "1") (pinfunction "1_1") (pintype "passive"))
      (node (ref "R35") (pin "1") (pinfunction "1_1") (pintype "passive"))
      (node (ref "R36") (pin "1") (pinfunction "1_1") (pintype "passive"))
    )
    (net (code "42") (name "Net-(D21-PadC)") (class "Default")
      (node (ref "D21") (pin "C") (pinfunction "C_C") (pintype "passive"))
      (node (ref "JP13") (pin "1") (pinfunction "1_1") (pintype "passive"))
      (node (ref "R38") (pin "1") (pinfunction "1_1") (pintype "passive"))
      (node (ref "R39") (pin "1") (pinfunction "1_1") (pintype "passive"))
    )
    (net (code "43") (name "Net-(IC1-VI)") (class "Default")
      (node (ref "C4") (pin "1") (pinfunction "1_1") (pintype "passive"))
      (node (ref "IC1") (pin "1") (pinfunction "VI_1") (pintype "input"))
      (node (ref "Q1") (pin "2") (pinfunction "S_2") (pintype "passive"))
    )
    (net (code "44") (name "Net-(L2-1)") (class "Default")
      (node (ref "L2") (pin "P$1") (pinfunction "1_P$1") (pintype "passive"))
      (node (ref "T1") (pin "+VOUT") (pinfunction "+VOUT_+VOUT") (pintype "bidirectional"))
    )
    (net (code "45") (name "Net-(LED1-PadA)") (class "Default")
      (node (ref "LED1") (pin "A") (pinfunction "A_A") (pintype "passive"))
      (node (ref "R5") (pin "2") (pinfunction "2_2") (pintype "passive"))
    )
    (net (code "46") (name "Net-(LED2-PadA)") (class "Default")
      (node (ref "LED2") (pin "A") (pinfunction "A_A") (pintype "passive"))
      (node (ref "R6") (pin "2") (pinfunction "2_2") (pintype "passive"))
    )
    (net (code "47") (name "Net-(LED3-PadA)") (class "Default")
      (node (ref "LED3") (pin "A") (pinfunction "A_A") (pintype "passive"))
      (node (ref "R7") (pin "2") (pinfunction "2_2") (pintype "passive"))
    )
    (net (code "48") (name "Net-(LED4-PadA)") (class "Default")
      (node (ref "LED4") (pin "A") (pinfunction "A_A") (pintype "passive"))
      (node (ref "R8") (pin "2") (pinfunction "2_2") (pintype "passive"))
    )
    (net (code "49") (name "Net-(LED5-PadA)") (class "Default")
      (node (ref "LED5") (pin "A") (pinfunction "A_A") (pintype "passive"))
      (node (ref "R40") (pin "2") (pinfunction "2_2") (pintype "passive"))
    )
    (net (code "50") (name "Net-(R9-Pad1)") (class "Default")
      (node (ref "R9") (pin "1") (pinfunction "1_1") (pintype "passive"))
      (node (ref "SW1") (pin "2") (pinfunction "2_2") (pintype "passive"))
    )
    (net (code "51") (name "Net-(R9-Pad2)") (class "Default")
      (node (ref "R9") (pin "2") (pinfunction "2_2") (pintype "passive"))
      (node (ref "SW1") (pin "1") (pinfunction "1_1") (pintype "passive"))
    )
    (net (code "52") (name "Net-(U$1-OSC1)") (class "Default")
      (node (ref "C1") (pin "1") (pinfunction "1_1") (pintype "passive"))
      (node (ref "U$1") (pin "8") (pinfunction "OSC1_8") (pintype "bidirectional"))
      (node (ref "Y1") (pin "1") (pinfunction "1_1") (pintype "passive"))
    )
    (net (code "53") (name "Net-(U$1-OSC2)") (class "Default")
      (node (ref "C3") (pin "1") (pinfunction "1_1") (pintype "passive"))
      (node (ref "U$1") (pin "7") (pinfunction "OSC2_7") (pintype "bidirectional"))
      (node (ref "Y1") (pin "2") (pinfunction "2_2") (pintype "passive"))
    )
    (net (code "54") (name "Net-(U$1-RESET{slash})") (class "Default")
      (node (ref "R4") (pin "2") (pinfunction "2_2") (pintype "passive"))
      (node (ref "U$1") (pin "17") (pinfunction "RESET/_17") (pintype "input"))
    )
    (net (code "55") (name "VCC-ISO") (class "Default")
      (node (ref "C9") (pin "1") (pinfunction "1_1") (pintype "passive"))
      (node (ref "D23") (pin "C") (pinfunction "C_C") (pintype "passive"))
      (node (ref "D24") (pin "C") (pinfunction "C_C") (pintype "passive"))
      (node (ref "D25") (pin "C") (pinfunction "C_C") (pintype "passive"))
      (node (ref "JP1") (pin "1") (pinfunction "1_1") (pintype "passive"))
      (node (ref "JP3") (pin "1") (pinfunction "1_1") (pintype "passive"))
      (node (ref "JP4") (pin "1") (pinfunction "1_1") (pintype "passive"))
      (node (ref "L1") (pin "2") (pinfunction "2_2") (pintype "passive"))
      (node (ref "Q1") (pin "3") (pinfunction "D_3") (pintype "passive"))
    )
    (net (code "56") (name "unconnected-(PCB2-Pad3V3)") (class "Default")
      (node (ref "PCB2") (pin "3V3") (pinfunction "3V3_3V3") (pintype "bidirectional"))
    )
    (net (code "57") (name "unconnected-(PCB2-PadREF)") (class "Default")
      (node (ref "PCB2") (pin "REF") (pinfunction "REF_REF") (pintype "bidirectional"))
    )
    (net (code "58") (name "unconnected-(PCB2-PadRST)") (class "Default")
      (node (ref "PCB2") (pin "RST") (pinfunction "RST_RST") (pintype "bidirectional"))
    )
    (net (code "59") (name "unconnected-(PCB2-PadRST.)") (class "Default")
      (node (ref "PCB2") (pin "RST.") (pinfunction "RST._RST.") (pintype "bidirectional"))
    )
    (net (code "60") (name "unconnected-(PCB2-PadTX1)") (class "Default")
      (node (ref "PCB2") (pin "TX1") (pinfunction "TX1_TX1") (pintype "bidirectional"))
    )
    (net (code "61") (name "unconnected-(PCB2-RX0-PadRX1)") (class "Default")
      (node (ref "PCB2") (pin "RX1") (pinfunction "RX0_RX1") (pintype "bidirectional"))
    )
    (net (code "62") (name "unconnected-(T1-NC*-PadNC+)") (class "Default")
      (node (ref "T1") (pin "NC+") (pinfunction "NC*_NC+") (pintype "bidirectional"))
    )
    (net (code "63") (name "unconnected-(T1-PadCTRL)") (class "Default")
      (node (ref "T1") (pin "CTRL") (pinfunction "CTRL_CTRL") (pintype "bidirectional"))
    )
    (net (code "64") (name "unconnected-(T1-PadNC)") (class "Default")
      (node (ref "T1") (pin "NC") (pinfunction "NC_NC") (pintype "bidirectional"))
    )
    (net (code "65") (name "unconnected-(U$1-CLKOUT{slash}SOF-Pad3)") (class "Default")
      (node (ref "U$1") (pin "3") (pinfunction "CLKOUT/SOF_3") (pintype "bidirectional"))
    )
    (net (code "66") (name "unconnected-(U$1-RX0BF{slash}-Pad11)") (class "Default")
      (node (ref "U$1") (pin "11") (pinfunction "RX0BF/_11") (pintype "bidirectional"))
    )
    (net (code "67") (name "unconnected-(U$1-RX1BF{slash}-Pad10)") (class "Default")
      (node (ref "U$1") (pin "10") (pinfunction "RX1BF/_10") (pintype "bidirectional"))
    )
    (net (code "68") (name "unconnected-(U$1-TX0RTS{slash}-Pad4)") (class "Default")
      (node (ref "U$1") (pin "4") (pinfunction "TX0RTS/_4") (pintype "bidirectional"))
    )
    (net (code "69") (name "unconnected-(U$1-TX1RTS{slash}-Pad5)") (class "Default")
      (node (ref "U$1") (pin "5") (pinfunction "TX1RTS/_5") (pintype "bidirectional"))
    )
    (net (code "70") (name "unconnected-(U$1-TX2RTS{slash}-Pad6)") (class "Default")
      (node (ref "U$1") (pin "6") (pinfunction "TX2RTS/_6") (pintype "bidirectional"))
    )
  )
)
